# Connectors.net
KiCad netlist of a schematic drawn in Altium Designer
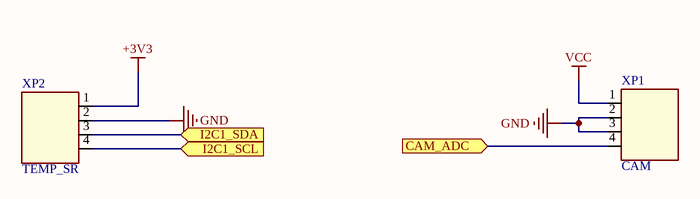
[diagram p0: Connectors.SchDoc]

(export (version "E")
  (design (tool "Eeschema 10.0.6"))
  (components
    (comp (ref "XP1")
      (value "CAM")
      (footprint "Connectors:HEAD-SMD-2.54/4")
      (libsource (lib "Connectors") (part "CON_4"))
    )
    (comp (ref "XP2")
      (value "TEMP_SR")
      (footprint "Connectors:HEAD-SMD-2.54/4")
      (libsource (lib "") (part "CON_4_1"))
    )
  )
  (nets
    (net (code "1") (name "+3V3") (class "Default")
      (node (ref "XP2") (pin "1") (pinfunction "1_1") (pintype "passive"))
    )
    (net (code "2") (name "/CAM_ADC") (class "Default")
      (node (ref "XP1") (pin "4") (pinfunction "4_4") (pintype "passive"))
    )
    (net (code "3") (name "/I2C1_SCL") (class "Default")
      (node (ref "XP2") (pin "4") (pinfunction "4_4") (pintype "passive"))
    )
    (net (code "4") (name "/I2C1_SDA") (class "Default")
      (node (ref "XP2") (pin "3") (pinfunction "3_3") (pintype "passive"))
    )
    (net (code "5") (name "GND") (class "Default")
      (node (ref "XP1") (pin "2") (pinfunction "2_2") (pintype "passive"))
      (node (ref "XP1") (pin "3") (pinfunction "3_3") (pintype "passive"))
      (node (ref "XP2") (pin "2") (pinfunction "2_2") (pintype "passive"))
    )
    (net (code "6") (name "VCC") (class "Default")
      (node (ref "XP1") (pin "1") (pinfunction "1_1") (pintype "passive"))
    )
  )
)
